# USB-UART-interface.net
KiCad netlist of a schematic drawn in Altium Designer
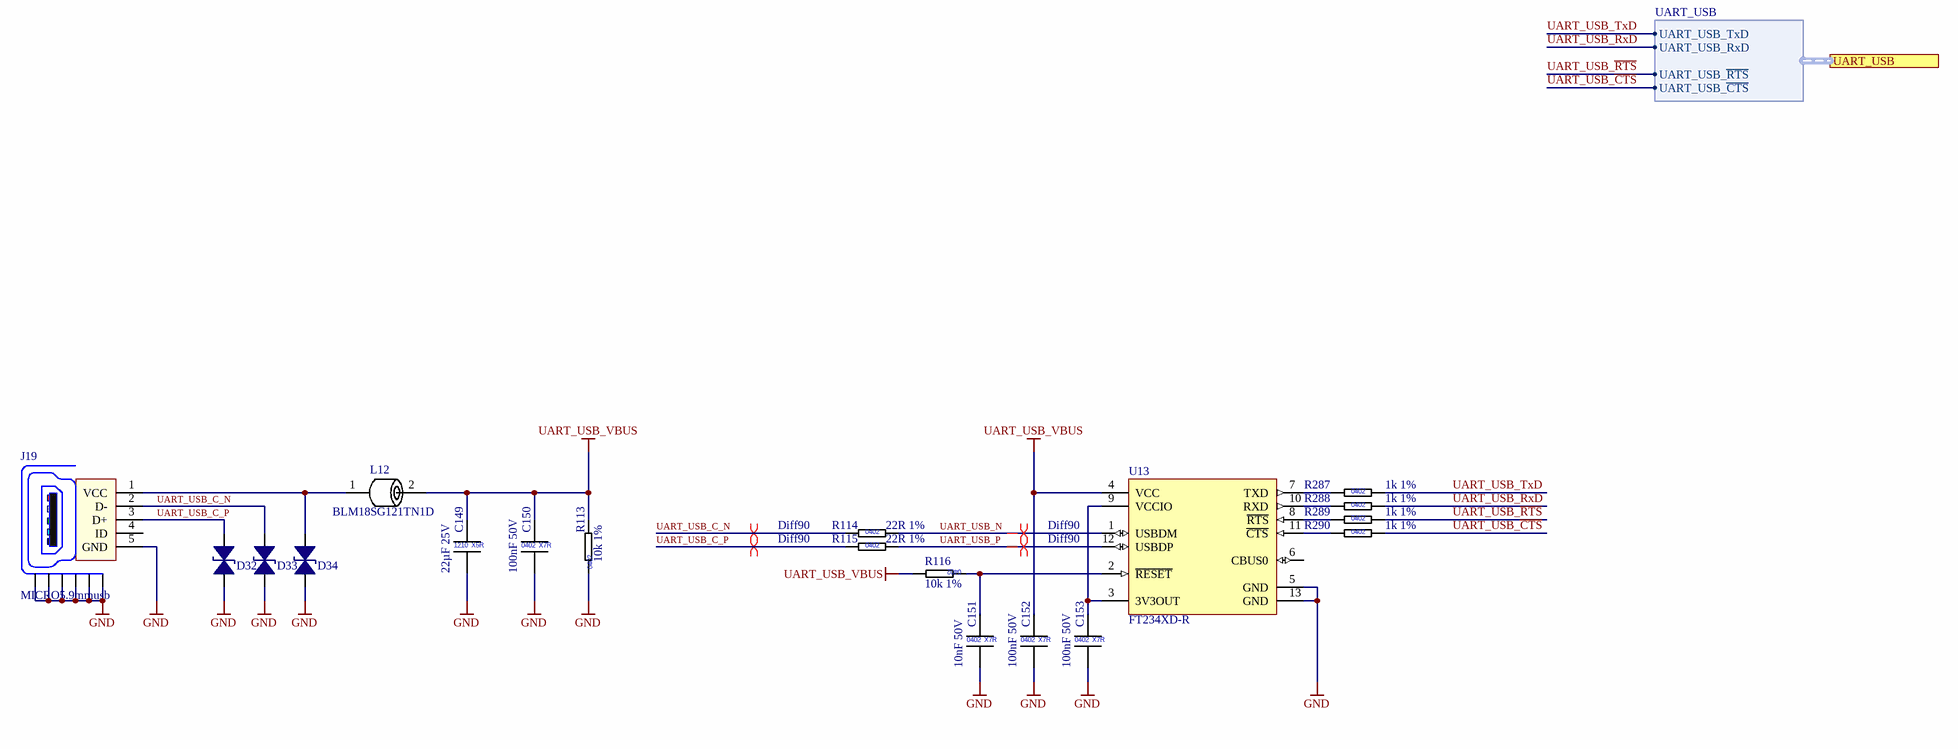
[diagram p0: USB-UART-interface.SchDoc]

(export (version "E")
  (design (tool "Eeschema 10.0.6"))
  (components
    (comp (ref "C149")
      (value "22µF 25V")
      (footprint "Cap:CAP_1210")
      (description "Multilayer Ceramic Capacitors MLCC - SMD/SMT 1210 25VDC")
      (libsource (lib "Cap") (part "CAP_1210_22µF_25V"))
    )
    (comp (ref "C150")
      (value "100nF 50V")
      (footprint "Cap:CAP_0402_L")
      (description "Multilayer Ceramic Capacitors MLCC - SMD/SMT 0402 50VDC")
      (libsource (lib "Cap") (part "CAP_0402_100nF_50V"))
    )
    (comp (ref "C151")
      (value "10nF 50V")
      (footprint "Cap:CAP_0402_L")
      (description "Multilayer Ceramic Capacitors MLCC - SMD/SMT 0402 50VDC")
      (libsource (lib "Cap") (part "CAP_0402_10nF_50V"))
    )
    (comp (ref "C152")
      (value "100nF 50V")
      (footprint "Cap:CAP_0402_L")
      (description "Multilayer Ceramic Capacitors MLCC - SMD/SMT 0402 50VDC")
      (libsource (lib "Cap") (part "CAP_0402_100nF_50V"))
    )
    (comp (ref "C153")
      (value "100nF 50V")
      (footprint "Cap:CAP_0402_L")
      (description "Multilayer Ceramic Capacitors MLCC - SMD/SMT 0402 50VDC")
      (libsource (lib "Cap") (part "CAP_0402_100nF_50V"))
    )
    (comp (ref "D32")
      (value "CESDP0402UC5VB")
      (footprint "Protec:TVS_0402")
      (description "Low Capacitance ESD Protection Diode 0402")
      (libsource (lib "Protec") (part "CESDP0402UC5VB_TVS Diode 0402"))
    )
    (comp (ref "D33")
      (value "CESDP0402UC5VB")
      (footprint "Protec:TVS_0402")
      (description "Low Capacitance ESD Protection Diode 0402")
      (libsource (lib "Protec") (part "CESDP0402UC5VB_TVS Diode 0402"))
    )
    (comp (ref "D34")
      (value "CESDP0402UC5VB")
      (footprint "Protec:TVS_0402")
      (description "Low Capacitance ESD Protection Diode 0402")
      (libsource (lib "Protec") (part "CESDP0402UC5VB_TVS Diode 0402"))
    )
    (comp (ref "J19")
      (value "MICRO5.9mmusb")
      (footprint "Conn:MICRO5.9mmusb")
      (description "SHOU HAN  MICRO5.9mmusb")
      (libsource (lib "Conn") (part "SMD micro USB Connector Horizontal C393940"))
    )
    (comp (ref "L12")
      (value "BLM18SG121TN1D")
      (footprint "Indc:L_0603")
      (description "Ferritperlen BLM18_xN 0603 100MHz 120Ohm 3000mA 25mOhm RSER")
      (libsource (lib "Indc") (part "BLM18SG121TN1D_Ferrite Beads 0603 120Ohms 3000mA"))
    )
    (comp (ref "R113")
      (value "10k 1%")
      (footprint "Res:RES_0402_L")
      (description "Thick Film Resistors - SMD 10kOhm 1%")
      (libsource (lib "Res") (part "RES_0402_10k_1%"))
    )
    (comp (ref "R114")
      (value "22R 1%")
      (footprint "Res:RES_0402_L")
      (description "Thick Film Resistors - SMD 22Ohm 1%")
      (libsource (lib "Res") (part "RES_0402_22R_1%"))
    )
    (comp (ref "R115")
      (value "22R 1%")
      (footprint "Res:RES_0402_L")
      (description "Thick Film Resistors - SMD 22Ohm 1%")
      (libsource (lib "Res") (part "RES_0402_22R_1%"))
    )
    (comp (ref "R116")
      (value "10k 1%")
      (footprint "Res:RES_0402_L")
      (description "Thick Film Resistors - SMD 10kOhm 1%")
      (libsource (lib "Res") (part "RES_0402_10k_1%"))
    )
    (comp (ref "R287")
      (value "1k 1%")
      (footprint "Res:RES_0402_L")
      (description "Thick Film Resistors - SMD 1kOhm 1%")
      (libsource (lib "Res") (part "RES_0402_1k_1%"))
    )
    (comp (ref "R288")
      (value "1k 1%")
      (footprint "Res:RES_0402_L")
      (description "Thick Film Resistors - SMD 1kOhm 1%")
      (libsource (lib "Res") (part "RES_0402_1k_1%"))
    )
    (comp (ref "R289")
      (value "1k 1%")
      (footprint "Res:RES_0402_L")
      (description "Thick Film Resistors - SMD 1kOhm 1%")
      (libsource (lib "Res") (part "RES_0402_1k_1%"))
    )
    (comp (ref "R290")
      (value "1k 1%")
      (footprint "Res:RES_0402_L")
      (description "Thick Film Resistors - SMD 1kOhm 1%")
      (libsource (lib "Res") (part "RES_0402_1k_1%"))
    )
    (comp (ref "U13")
      (value "FT234XD-R")
      (footprint "digital:QFN45P300X300x75_-12N")
      (description "IC USB SERIAL BASIC UART 12DFN")
      (libsource (lib "Digital") (part "FT234XD-R_IC USB SERIAL BASIC UART 12DFN"))
    )
  )
  (nets
    (net (code "2") (name "/UART_USB_C_N") (class "Default")
      (node (ref "D33") (pin "1") (pinfunction "1_1") (pintype "passive"))
      (node (ref "J19") (pin "2") (pinfunction "D-_2") (pintype "passive"))
      (node (ref "R114") (pin "1") (pinfunction "1_1") (pintype "passive"))
    )
    (net (code "3") (name "/UART_USB_C_P") (class "Default")
      (node (ref "D32") (pin "1") (pinfunction "1_1") (pintype "passive"))
      (node (ref "J19") (pin "3") (pinfunction "D+_3") (pintype "passive"))
      (node (ref "R115") (pin "1") (pinfunction "1_1") (pintype "passive"))
    )
    (net (code "4") (name "/UART_USB_N") (class "Default")
      (node (ref "R114") (pin "2") (pinfunction "2_2") (pintype "passive"))
      (node (ref "U13") (pin "1") (pinfunction "USBDM_1") (pintype "bidirectional"))
    )
    (net (code "5") (name "/UART_USB_P") (class "Default")
      (node (ref "R115") (pin "2") (pinfunction "2_2") (pintype "passive"))
      (node (ref "U13") (pin "12") (pinfunction "USBDP_12") (pintype "bidirectional"))
    )
    (net (code "6") (name "/UART_USB_RxD") (class "Default")
      (node (ref "R288") (pin "2") (pinfunction "2_2") (pintype "passive"))
    )
    (net (code "7") (name "/UART_USB_TxD") (class "Default")
      (node (ref "R287") (pin "2") (pinfunction "2_2") (pintype "passive"))
    )
    (net (code "8") (name "/UART_USB_~{CTS}") (class "Default")
      (node (ref "R290") (pin "2") (pinfunction "2_2") (pintype "passive"))
    )
    (net (code "9") (name "/UART_USB_~{RTS}") (class "Default")
      (node (ref "R289") (pin "2") (pinfunction "2_2") (pintype "passive"))
    )
    (net (code "11") (name "GND") (class "Default")
      (node (ref "C149") (pin "2") (pinfunction "2_2") (pintype "passive"))
      (node (ref "C150") (pin "2") (pinfunction "2_2") (pintype "passive"))
      (node (ref "C151") (pin "2") (pinfunction "2_2") (pintype "passive"))
      (node (ref "C152") (pin "2") (pinfunction "2_2") (pintype "passive"))
      (node (ref "C153") (pin "2") (pinfunction "2_2") (pintype "passive"))
      (node (ref "D32") (pin "2") (pinfunction "2_2") (pintype "passive"))
      (node (ref "D33") (pin "2") (pinfunction "2_2") (pintype "passive"))
      (node (ref "D34") (pin "2") (pinfunction "2_2") (pintype "passive"))
      (node (ref "J19") (pin "10") (pinfunction "Shield_10") (pintype "passive"))
      (node (ref "J19") (pin "11") (pinfunction "Shield_11") (pintype "passive"))
      (node (ref "J19") (pin "5") (pinfunction "GND_5") (pintype "passive"))
      (node (ref "J19") (pin "6") (pinfunction "Shield_6") (pintype "passive"))
      (node (ref "J19") (pin "7") (pinfunction "Shield_7") (pintype "passive"))
      (node (ref "J19") (pin "8") (pinfunction "Shield_8") (pintype "passive"))
      (node (ref "J19") (pin "9") (pinfunction "Shield_9") (pintype "passive"))
      (node (ref "R113") (pin "1") (pinfunction "1_1") (pintype "passive"))
      (node (ref "U13") (pin "13") (pinfunction "GND_13") (pintype "power_in"))
      (node (ref "U13") (pin "5") (pinfunction "GND_5") (pintype "power_in"))
    )
    (net (code "12") (name "Net-(J19-VCC)") (class "Default")
      (node (ref "D34") (pin "1") (pinfunction "1_1") (pintype "passive"))
      (node (ref "J19") (pin "1") (pinfunction "VCC_1") (pintype "passive"))
      (node (ref "L12") (pin "1") (pinfunction "1_1") (pintype "passive"))
    )
    (net (code "13") (name "Net-(U13-3V3OUT)") (class "Default")
      (node (ref "C153") (pin "1") (pinfunction "1_1") (pintype "passive"))
      (node (ref "U13") (pin "3") (pinfunction "3V3OUT_3") (pintype "power_in"))
      (node (ref "U13") (pin "9") (pinfunction "VCCIO_9") (pintype "power_in"))
    )
    (net (code "14") (name "Net-(U13-RXD)") (class "Default")
      (node (ref "R288") (pin "1") (pinfunction "1_1") (pintype "passive"))
      (node (ref "U13") (pin "10") (pinfunction "RXD_10") (pintype "output"))
    )
    (net (code "15") (name "Net-(U13-TXD)") (class "Default")
      (node (ref "R287") (pin "1") (pinfunction "1_1") (pintype "passive"))
      (node (ref "U13") (pin "7") (pinfunction "TXD_7") (pintype "output"))
    )
    (net (code "16") (name "Net-(U13-~{CTS})") (class "Default")
      (node (ref "R290") (pin "1") (pinfunction "1_1") (pintype "passive"))
      (node (ref "U13") (pin "11") (pinfunction "~{CTS}_11") (pintype "input"))
    )
    (net (code "17") (name "Net-(U13-~{RESET})") (class "Default")
      (node (ref "C151") (pin "1") (pinfunction "1_1") (pintype "passive"))
      (node (ref "R116") (pin "1") (pinfunction "1_1") (pintype "passive"))
      (node (ref "U13") (pin "2") (pinfunction "~{RESET}_2") (pintype "input"))
    )
    (net (code "18") (name "Net-(U13-~{RTS})") (class "Default")
      (node (ref "R289") (pin "1") (pinfunction "1_1") (pintype "passive"))
      (node (ref "U13") (pin "8") (pinfunction "~{RTS}_8") (pintype "input"))
    )
    (net (code "19") (name "UART_USB_VBUS") (class "Default")
      (node (ref "C149") (pin "1") (pinfunction "1_1") (pintype "passive"))
      (node (ref "C150") (pin "1") (pinfunction "1_1") (pintype "passive"))
      (node (ref "C152") (pin "1") (pinfunction "1_1") (pintype "passive"))
      (node (ref "L12") (pin "2") (pinfunction "2_2") (pintype "passive"))
      (node (ref "R113") (pin "2") (pinfunction "2_2") (pintype "passive"))
      (node (ref "R116") (pin "2") (pinfunction "2_2") (pintype "passive"))
      (node (ref "U13") (pin "4") (pinfunction "VCC_4") (pintype "power_in"))
    )
    (net (code "20") (name "unconnected-(J19-ID-Pad4)") (class "Default")
      (node (ref "J19") (pin "4") (pinfunction "ID_4") (pintype "passive"))
    )
    (net (code "21") (name "unconnected-(U13-CBUS0-Pad6)") (class "Default")
      (node (ref "U13") (pin "6") (pinfunction "CBUS0_6") (pintype "bidirectional"))
    )
  )
)
